# SCH_555-Circuit_2025-03-12.net
KiCad netlist of a schematic drawn in EasyEDA
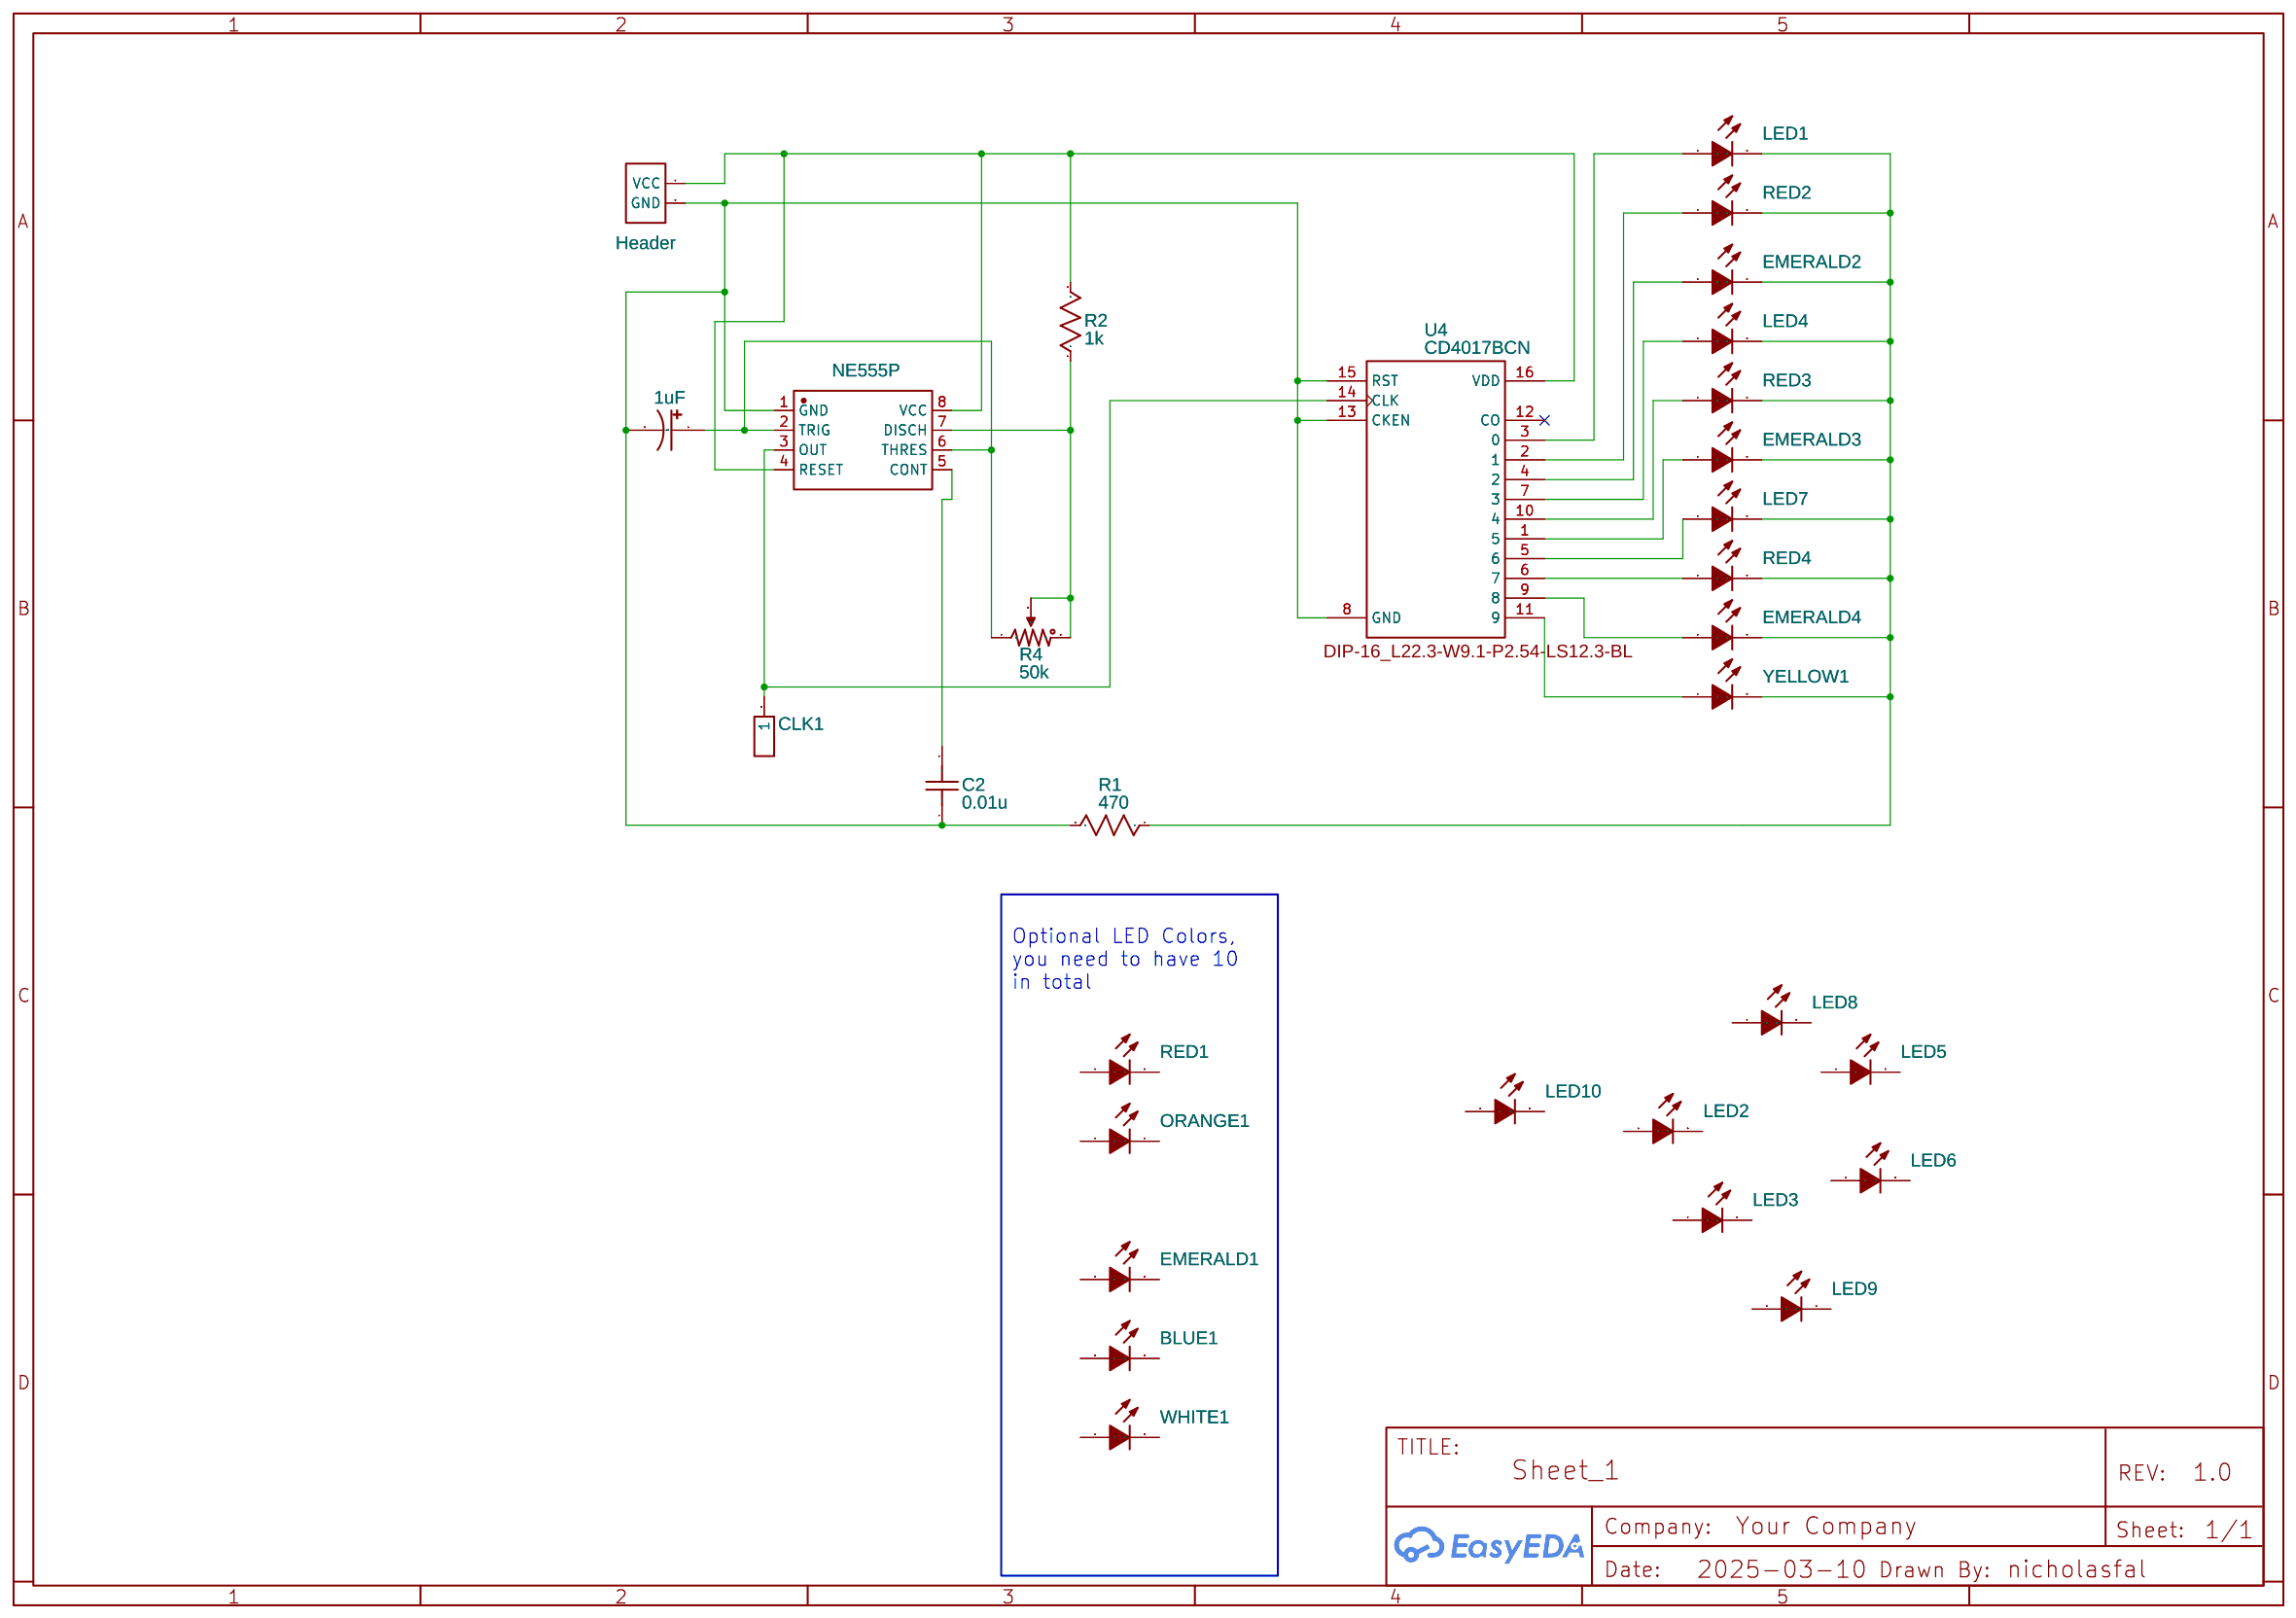
[diagram p0: schematic sheet]

(export (version "E")
  (design (tool "Eeschema 10.0.6"))
  (components
    (comp (ref "BLUE1") (value "LED_5MM") (libsource (lib "") (part "LED_5MM_4")))
    (comp (ref "C1")
      (value "1uF")
      (fields (field (name "Manufacturer Part") "UVZ1H010MDD") (field (name "Manufacturer") "Nichicon(尼吉康)"))
      (libsource (lib "") (part "UVZ1H010MDD"))
    )
    (comp (ref "C2") (value "0.01u") (libsource (lib "") (part "C_0603_US")))
    (comp (ref "CLK1")
      (value "C81276")
      (fields
        (field (name "Manufacturer Part") "2.54-1*1P针")
        (field (name "Manufacturer") "BOOMELE(Boom Precision Elec)")
      )
      (libsource (lib "") (part "Header-Male-2.54_1x1"))
    )
    (comp (ref "EMERALD1") (value "LED_5MM") (libsource (lib "") (part "LED_5MM_2")))
    (comp (ref "EMERALD2") (value "LED_5MM") (libsource (lib "") (part "LED_5MM_2")))
    (comp (ref "EMERALD3") (value "LED_5MM") (libsource (lib "") (part "LED_5MM_2")))
    (comp (ref "EMERALD4") (value "LED_5MM") (libsource (lib "") (part "LED_5MM_2")))
    (comp (ref "H1") (value "Header") (libsource (lib "") (part "HEADER-FEMALE-2.54_1X2")))
    (comp (ref "LED1") (value "LED_5MM") (libsource (lib "") (part "LED_5MM")))
    (comp (ref "LED2") (value "LED_5MM") (libsource (lib "") (part "LED_5MM")))
    (comp (ref "LED3") (value "LED_5MM") (libsource (lib "") (part "LED_5MM")))
    (comp (ref "LED4") (value "LED_5MM") (libsource (lib "") (part "LED_5MM")))
    (comp (ref "LED5") (value "LED_5MM") (libsource (lib "") (part "LED_5MM")))
    (comp (ref "LED6") (value "LED_5MM") (libsource (lib "") (part "LED_5MM")))
    (comp (ref "LED7") (value "LED_5MM") (libsource (lib "") (part "LED_5MM")))
    (comp (ref "LED8") (value "LED_5MM") (libsource (lib "") (part "LED_5MM")))
    (comp (ref "LED9") (value "LED_5MM") (libsource (lib "") (part "LED_5MM")))
    (comp (ref "LED10") (value "LED_5MM") (libsource (lib "") (part "LED_5MM")))
    (comp (ref "ORANGE1") (value "LED_5MM") (libsource (lib "") (part "LED_5MM_5")))
    (comp (ref "R1")
      (value "470")
      (fields (field (name "Manufacturer Part") "?"))
      (libsource (lib "") (part "Resistor_1"))
    )
    (comp (ref "R2")
      (value "1k")
      (fields (field (name "Manufacturer Part") "?"))
      (libsource (lib "") (part "Resistor"))
    )
    (comp (ref "R4")
      (value "50k")
      (fields (field (name "Manufacturer Part") "?"))
      (libsource (lib "") (part "Potentiometer"))
    )
    (comp (ref "RED1") (value "LED_5MM") (libsource (lib "") (part "LED_5MM_1")))
    (comp (ref "RED2") (value "LED_5MM") (libsource (lib "") (part "LED_5MM_1")))
    (comp (ref "RED3") (value "LED_5MM") (libsource (lib "") (part "LED_5MM_1")))
    (comp (ref "RED4") (value "LED_5MM") (libsource (lib "") (part "LED_5MM_1")))
    (comp (ref "U2")
      (value "NE555P")
      (fields (field (name "Manufacturer") "TI(德州仪器)"))
      (libsource (lib "") (part "NE555P"))
    )
    (comp (ref "U4") (value "CD4017BCN") (libsource (lib "") (part "CD4017BCN")))
    (comp (ref "WHITE1") (value "LED_5MM") (libsource (lib "") (part "LED_5MM_6")))
    (comp (ref "YELLOW1") (value "LED_5MM") (libsource (lib "") (part "LED_5MM_3")))
  )
  (nets
    (net (code "1") (name "Net-(EMERALD2-A)") (class "Default")
      (node (ref "EMERALD2") (pin "1") (pinfunction "A_1") (pintype "input"))
      (node (ref "U4") (pin "4") (pinfunction "2_4") (pintype "output"))
    )
    (net (code "2") (name "Net-(EMERALD2-K)") (class "Default")
      (node (ref "EMERALD2") (pin "2") (pinfunction "K_2") (pintype "input"))
      (node (ref "EMERALD3") (pin "2") (pinfunction "K_2") (pintype "input"))
      (node (ref "EMERALD4") (pin "2") (pinfunction "K_2") (pintype "input"))
      (node (ref "LED1") (pin "2") (pinfunction "K_2") (pintype "input"))
      (node (ref "LED4") (pin "2") (pinfunction "K_2") (pintype "input"))
      (node (ref "LED7") (pin "2") (pinfunction "K_2") (pintype "input"))
      (node (ref "R1") (pin "1") (pinfunction "1_1") (pintype "unspecified"))
      (node (ref "RED2") (pin "2") (pinfunction "K_2") (pintype "input"))
      (node (ref "RED3") (pin "2") (pinfunction "K_2") (pintype "input"))
      (node (ref "RED4") (pin "2") (pinfunction "K_2") (pintype "input"))
      (node (ref "YELLOW1") (pin "2") (pinfunction "K_2") (pintype "input"))
    )
    (net (code "3") (name "Net-(EMERALD3-A)") (class "Default")
      (node (ref "EMERALD3") (pin "1") (pinfunction "A_1") (pintype "input"))
      (node (ref "U4") (pin "1") (pinfunction "5_1") (pintype "output"))
    )
    (net (code "4") (name "Net-(EMERALD4-A)") (class "Default")
      (node (ref "EMERALD4") (pin "1") (pinfunction "A_1") (pintype "input"))
      (node (ref "U4") (pin "9") (pinfunction "8_9") (pintype "output"))
    )
    (net (code "5") (name "Net-(H1-GND)") (class "Default")
      (node (ref "C1") (pin "2") (pinfunction "2_2") (pintype "unspecified"))
      (node (ref "C2") (pin "1") (pinfunction "1_1") (pintype "unspecified"))
      (node (ref "H1") (pin "2") (pinfunction "GND_2") (pintype "unspecified"))
      (node (ref "R1") (pin "2") (pinfunction "2_2") (pintype "unspecified"))
      (node (ref "U2") (pin "1") (pinfunction "GND_1") (pintype "unspecified"))
      (node (ref "U4") (pin "13") (pinfunction "CKEN_13") (pintype "unspecified"))
      (node (ref "U4") (pin "15") (pinfunction "RST_15") (pintype "unspecified"))
      (node (ref "U4") (pin "8") (pinfunction "GND_8") (pintype "passive"))
    )
    (net (code "6") (name "Net-(H1-VCC)") (class "Default")
      (node (ref "H1") (pin "1") (pinfunction "VCC_1") (pintype "unspecified"))
      (node (ref "R2") (pin "2") (pinfunction "2_2") (pintype "unspecified"))
      (node (ref "U2") (pin "4") (pinfunction "RESET_4") (pintype "unspecified"))
      (node (ref "U2") (pin "8") (pinfunction "VCC_8") (pintype "unspecified"))
      (node (ref "U4") (pin "16") (pinfunction "VDD_16") (pintype "passive"))
    )
    (net (code "7") (name "Net-(LED1-A)") (class "Default")
      (node (ref "LED1") (pin "1") (pinfunction "A_1") (pintype "input"))
      (node (ref "U4") (pin "3") (pinfunction "0_3") (pintype "output"))
    )
    (net (code "8") (name "Net-(LED4-A)") (class "Default")
      (node (ref "LED4") (pin "1") (pinfunction "A_1") (pintype "input"))
      (node (ref "U4") (pin "7") (pinfunction "3_7") (pintype "output"))
    )
    (net (code "9") (name "Net-(LED7-A)") (class "Default")
      (node (ref "LED7") (pin "1") (pinfunction "A_1") (pintype "input"))
      (node (ref "U4") (pin "5") (pinfunction "6_5") (pintype "output"))
    )
    (net (code "10") (name "Net-(R4-2)") (class "Default")
      (node (ref "R2") (pin "1") (pinfunction "1_1") (pintype "unspecified"))
      (node (ref "R4") (pin "2") (pinfunction "3_2") (pintype "unspecified"))
      (node (ref "R4") (pin "3") (pinfunction "2_3") (pintype "unspecified"))
      (node (ref "U2") (pin "7") (pinfunction "DISCH_7") (pintype "unspecified"))
    )
    (net (code "11") (name "Net-(RED2-A)") (class "Default")
      (node (ref "RED2") (pin "1") (pinfunction "A_1") (pintype "input"))
      (node (ref "U4") (pin "2") (pinfunction "1_2") (pintype "output"))
    )
    (net (code "12") (name "Net-(RED3-A)") (class "Default")
      (node (ref "RED3") (pin "1") (pinfunction "A_1") (pintype "input"))
      (node (ref "U4") (pin "10") (pinfunction "4_10") (pintype "output"))
    )
    (net (code "13") (name "Net-(RED4-A)") (class "Default")
      (node (ref "RED4") (pin "1") (pinfunction "A_1") (pintype "input"))
      (node (ref "U4") (pin "6") (pinfunction "7_6") (pintype "output"))
    )
    (net (code "14") (name "Net-(U2-CONT)") (class "Default")
      (node (ref "C2") (pin "2") (pinfunction "2_2") (pintype "unspecified"))
      (node (ref "U2") (pin "5") (pinfunction "CONT_5") (pintype "unspecified"))
    )
    (net (code "15") (name "Net-(U2-OUT)") (class "Default")
      (node (ref "CLK1") (pin "1") (pinfunction "1_1") (pintype "unspecified"))
      (node (ref "U2") (pin "3") (pinfunction "OUT_3") (pintype "unspecified"))
      (node (ref "U4") (pin "14") (pinfunction "CLK_14") (pintype "unspecified"))
    )
    (net (code "16") (name "Net-(U2-THRES)") (class "Default")
      (node (ref "C1") (pin "1") (pinfunction "1_1") (pintype "unspecified"))
      (node (ref "R4") (pin "1") (pinfunction "1_1") (pintype "unspecified"))
      (node (ref "U2") (pin "2") (pinfunction "TRIG_2") (pintype "unspecified"))
      (node (ref "U2") (pin "6") (pinfunction "THRES_6") (pintype "unspecified"))
    )
    (net (code "17") (name "Net-(U4-9)") (class "Default")
      (node (ref "U4") (pin "11") (pinfunction "9_11") (pintype "output"))
      (node (ref "YELLOW1") (pin "1") (pinfunction "A_1") (pintype "input"))
    )
    (net (code "18") (name "unconnected-(BLUE1-A-Pad1)") (class "Default")
      (node (ref "BLUE1") (pin "1") (pinfunction "A_1") (pintype "input"))
    )
    (net (code "19") (name "unconnected-(BLUE1-K-Pad2)") (class "Default")
      (node (ref "BLUE1") (pin "2") (pinfunction "K_2") (pintype "input"))
    )
    (net (code "20") (name "unconnected-(EMERALD1-A-Pad1)") (class "Default")
      (node (ref "EMERALD1") (pin "1") (pinfunction "A_1") (pintype "input"))
    )
    (net (code "21") (name "unconnected-(EMERALD1-K-Pad2)") (class "Default")
      (node (ref "EMERALD1") (pin "2") (pinfunction "K_2") (pintype "input"))
    )
    (net (code "22") (name "unconnected-(LED2-A-Pad1)") (class "Default")
      (node (ref "LED2") (pin "1") (pinfunction "A_1") (pintype "input"))
    )
    (net (code "23") (name "unconnected-(LED2-K-Pad2)") (class "Default")
      (node (ref "LED2") (pin "2") (pinfunction "K_2") (pintype "input"))
    )
    (net (code "24") (name "unconnected-(LED3-A-Pad1)") (class "Default")
      (node (ref "LED3") (pin "1") (pinfunction "A_1") (pintype "input"))
    )
    (net (code "25") (name "unconnected-(LED3-K-Pad2)") (class "Default")
      (node (ref "LED3") (pin "2") (pinfunction "K_2") (pintype "input"))
    )
    (net (code "26") (name "unconnected-(LED5-A-Pad1)") (class "Default")
      (node (ref "LED5") (pin "1") (pinfunction "A_1") (pintype "input"))
    )
    (net (code "27") (name "unconnected-(LED5-K-Pad2)") (class "Default")
      (node (ref "LED5") (pin "2") (pinfunction "K_2") (pintype "input"))
    )
    (net (code "28") (name "unconnected-(LED6-A-Pad1)") (class "Default")
      (node (ref "LED6") (pin "1") (pinfunction "A_1") (pintype "input"))
    )
    (net (code "29") (name "unconnected-(LED6-K-Pad2)") (class "Default")
      (node (ref "LED6") (pin "2") (pinfunction "K_2") (pintype "input"))
    )
    (net (code "30") (name "unconnected-(LED8-A-Pad1)") (class "Default")
      (node (ref "LED8") (pin "1") (pinfunction "A_1") (pintype "input"))
    )
    (net (code "31") (name "unconnected-(LED8-K-Pad2)") (class "Default")
      (node (ref "LED8") (pin "2") (pinfunction "K_2") (pintype "input"))
    )
    (net (code "32") (name "unconnected-(LED9-A-Pad1)") (class "Default")
      (node (ref "LED9") (pin "1") (pinfunction "A_1") (pintype "input"))
    )
    (net (code "33") (name "unconnected-(LED9-K-Pad2)") (class "Default")
      (node (ref "LED9") (pin "2") (pinfunction "K_2") (pintype "input"))
    )
    (net (code "34") (name "unconnected-(LED10-A-Pad1)") (class "Default")
      (node (ref "LED10") (pin "1") (pinfunction "A_1") (pintype "input"))
    )
    (net (code "35") (name "unconnected-(LED10-K-Pad2)") (class "Default")
      (node (ref "LED10") (pin "2") (pinfunction "K_2") (pintype "input"))
    )
    (net (code "36") (name "unconnected-(ORANGE1-A-Pad1)") (class "Default")
      (node (ref "ORANGE1") (pin "1") (pinfunction "A_1") (pintype "input"))
    )
    (net (code "37") (name "unconnected-(ORANGE1-K-Pad2)") (class "Default")
      (node (ref "ORANGE1") (pin "2") (pinfunction "K_2") (pintype "input"))
    )
    (net (code "38") (name "unconnected-(RED1-A-Pad1)") (class "Default")
      (node (ref "RED1") (pin "1") (pinfunction "A_1") (pintype "input"))
    )
    (net (code "39") (name "unconnected-(RED1-K-Pad2)") (class "Default")
      (node (ref "RED1") (pin "2") (pinfunction "K_2") (pintype "input"))
    )
    (net (code "40") (name "unconnected-(U4-CO-Pad12)") (class "Default")
      (node (ref "U4") (pin "12") (pinfunction "CO_12") (pintype "output+no_connect"))
    )
    (net (code "41") (name "unconnected-(WHITE1-A-Pad1)") (class "Default")
      (node (ref "WHITE1") (pin "1") (pinfunction "A_1") (pintype "input"))
    )
    (net (code "42") (name "unconnected-(WHITE1-K-Pad2)") (class "Default")
      (node (ref "WHITE1") (pin "2") (pinfunction "K_2") (pintype "input"))
    )
  )
)
